# FPGA_PWR.net
KiCad netlist of a schematic drawn in Altium Designer
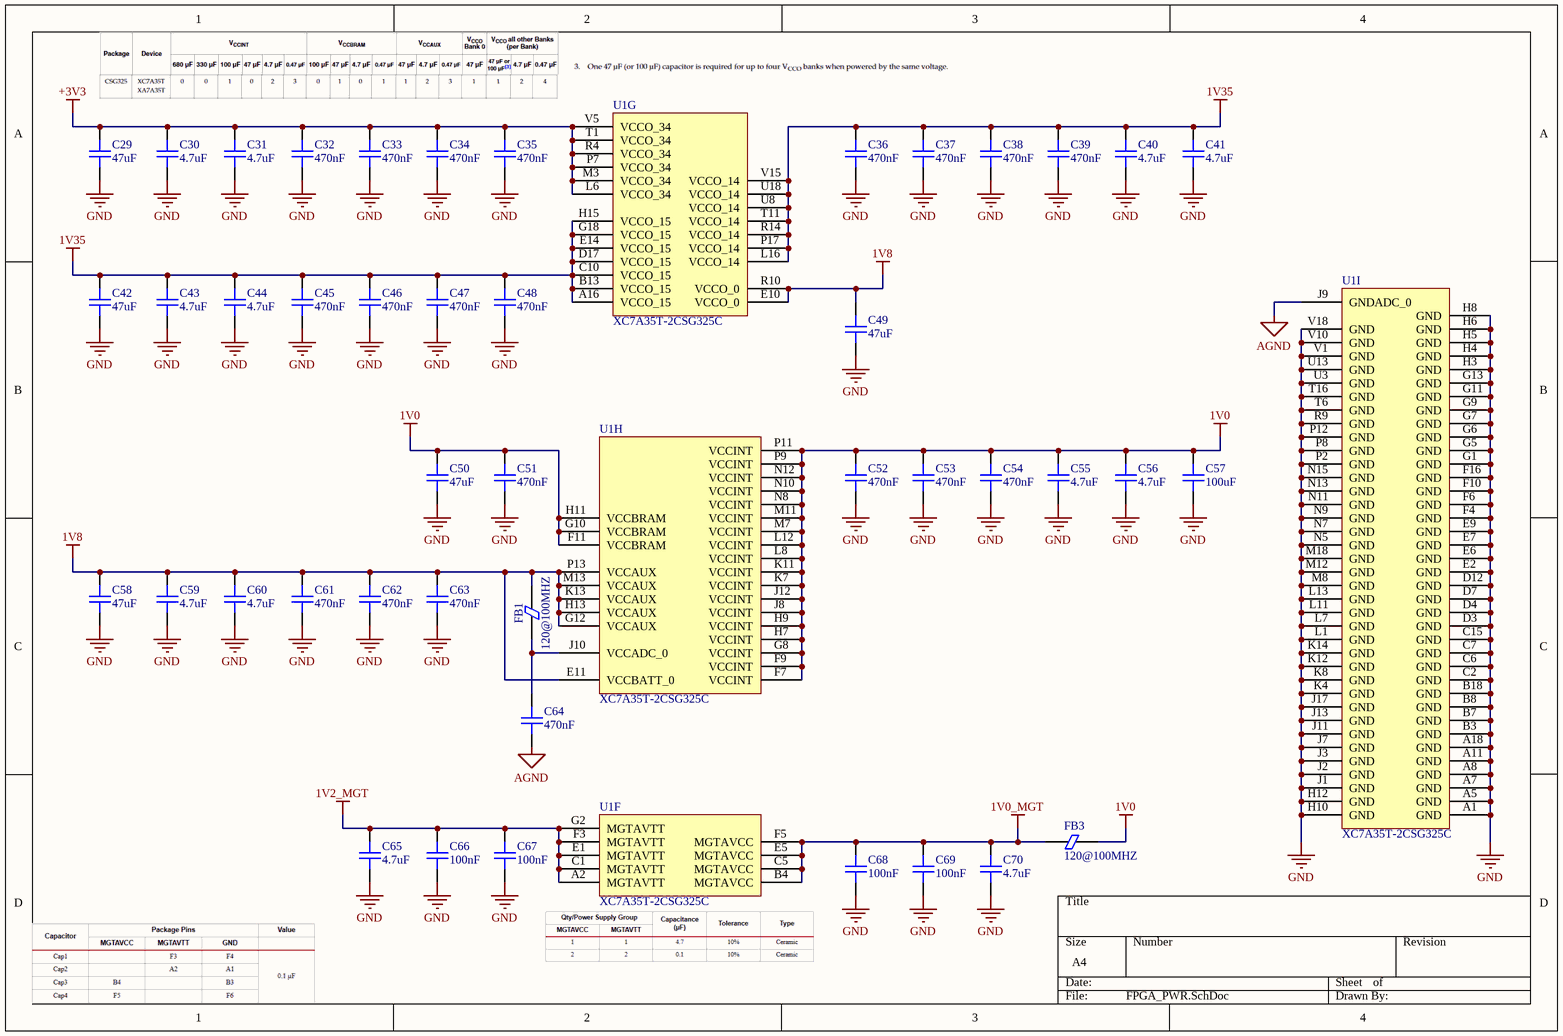
[diagram p0: FPGA_PWR.SchDoc]

(export (version "E")
  (design (tool "Eeschema 10.0.6"))
  (components
    (comp (ref "C29")
      (value "47uF")
      (footprint "GEN_C_0805")
      (libsource (lib "DSO") (part "CAP 47uF 6.3V X5R 0805"))
    )
    (comp (ref "C30")
      (value "4.7uF")
      (footprint "GEN_C_0402")
      (libsource (lib "DSO") (part "CAP 4.7uF 6.3V X5R 0402"))
    )
    (comp (ref "C31")
      (value "4.7uF")
      (footprint "GEN_C_0402")
      (libsource (lib "DSO") (part "CAP 4.7uF 6.3V X5R 0402"))
    )
    (comp (ref "C32")
      (value "470nF")
      (footprint "GEN_C_0201")
      (libsource (lib "DSO") (part "CAP 470nF 6.3V X5R 0201"))
    )
    (comp (ref "C33")
      (value "470nF")
      (footprint "GEN_C_0201")
      (libsource (lib "DSO") (part "CAP 470nF 6.3V X5R 0201"))
    )
    (comp (ref "C34")
      (value "470nF")
      (footprint "GEN_C_0201")
      (libsource (lib "DSO") (part "CAP 470nF 6.3V X5R 0201"))
    )
    (comp (ref "C35")
      (value "470nF")
      (footprint "GEN_C_0201")
      (libsource (lib "DSO") (part "CAP 470nF 6.3V X5R 0201"))
    )
    (comp (ref "C36")
      (value "470nF")
      (footprint "GEN_C_0201")
      (libsource (lib "DSO") (part "CAP 470nF 6.3V X5R 0201"))
    )
    (comp (ref "C37")
      (value "470nF")
      (footprint "GEN_C_0201")
      (libsource (lib "DSO") (part "CAP 470nF 6.3V X5R 0201"))
    )
    (comp (ref "C38")
      (value "470nF")
      (footprint "GEN_C_0201")
      (libsource (lib "DSO") (part "CAP 470nF 6.3V X5R 0201"))
    )
    (comp (ref "C39")
      (value "470nF")
      (footprint "GEN_C_0201")
      (libsource (lib "DSO") (part "CAP 470nF 6.3V X5R 0201"))
    )
    (comp (ref "C40")
      (value "4.7uF")
      (footprint "GEN_C_0402")
      (libsource (lib "DSO") (part "CAP 4.7uF 6.3V X5R 0402"))
    )
    (comp (ref "C41")
      (value "4.7uF")
      (footprint "GEN_C_0402")
      (libsource (lib "DSO") (part "CAP 4.7uF 6.3V X5R 0402"))
    )
    (comp (ref "C42")
      (value "47uF")
      (footprint "GEN_C_0805")
      (libsource (lib "DSO") (part "CAP 47uF 6.3V X5R 0805"))
    )
    (comp (ref "C43")
      (value "4.7uF")
      (footprint "GEN_C_0402")
      (libsource (lib "DSO") (part "CAP 4.7uF 6.3V X5R 0402"))
    )
    (comp (ref "C44")
      (value "4.7uF")
      (footprint "GEN_C_0402")
      (libsource (lib "DSO") (part "CAP 4.7uF 6.3V X5R 0402"))
    )
    (comp (ref "C45")
      (value "470nF")
      (footprint "GEN_C_0201")
      (libsource (lib "DSO") (part "CAP 470nF 6.3V X5R 0201"))
    )
    (comp (ref "C46")
      (value "470nF")
      (footprint "GEN_C_0201")
      (libsource (lib "DSO") (part "CAP 470nF 6.3V X5R 0201"))
    )
    (comp (ref "C47")
      (value "470nF")
      (footprint "GEN_C_0201")
      (libsource (lib "DSO") (part "CAP 470nF 6.3V X5R 0201"))
    )
    (comp (ref "C48")
      (value "470nF")
      (footprint "GEN_C_0201")
      (libsource (lib "DSO") (part "CAP 470nF 6.3V X5R 0201"))
    )
    (comp (ref "C49")
      (value "47uF")
      (footprint "GEN_C_0805")
      (libsource (lib "DSO") (part "CAP 47uF 6.3V X5R 0805"))
    )
    (comp (ref "C50")
      (value "47uF")
      (footprint "GEN_C_0805")
      (libsource (lib "DSO") (part "CAP 47uF 6.3V X5R 0805"))
    )
    (comp (ref "C51")
      (value "470nF")
      (footprint "GEN_C_0201")
      (libsource (lib "DSO") (part "CAP 470nF 6.3V X5R 0201"))
    )
    (comp (ref "C52")
      (value "470nF")
      (footprint "GEN_C_0201")
      (libsource (lib "DSO") (part "CAP 470nF 6.3V X5R 0201"))
    )
    (comp (ref "C53")
      (value "470nF")
      (footprint "GEN_C_0201")
      (libsource (lib "DSO") (part "CAP 470nF 6.3V X5R 0201"))
    )
    (comp (ref "C54")
      (value "470nF")
      (footprint "GEN_C_0201")
      (libsource (lib "DSO") (part "CAP 470nF 6.3V X5R 0201"))
    )
    (comp (ref "C55")
      (value "4.7uF")
      (footprint "GEN_C_0402")
      (libsource (lib "DSO") (part "CAP 4.7uF 6.3V X5R 0402"))
    )
    (comp (ref "C56")
      (value "4.7uF")
      (footprint "GEN_C_0402")
      (libsource (lib "DSO") (part "CAP 4.7uF 6.3V X5R 0402"))
    )
    (comp (ref "C57")
      (value "100uF")
      (footprint "GEN_C_1210")
      (libsource (lib "DSO") (part "CAP 100uF 6.3V X5R 1210"))
    )
    (comp (ref "C58")
      (value "47uF")
      (footprint "GEN_C_0805")
      (libsource (lib "DSO") (part "CAP 47uF 6.3V X5R 0805"))
    )
    (comp (ref "C59")
      (value "4.7uF")
      (footprint "GEN_C_0402")
      (libsource (lib "DSO") (part "CAP 4.7uF 6.3V X5R 0402"))
    )
    (comp (ref "C60")
      (value "4.7uF")
      (footprint "GEN_C_0402")
      (libsource (lib "DSO") (part "CAP 4.7uF 6.3V X5R 0402"))
    )
    (comp (ref "C61")
      (value "470nF")
      (footprint "GEN_C_0201")
      (libsource (lib "DSO") (part "CAP 470nF 6.3V X5R 0201"))
    )
    (comp (ref "C62")
      (value "470nF")
      (footprint "GEN_C_0201")
      (libsource (lib "DSO") (part "CAP 470nF 6.3V X5R 0201"))
    )
    (comp (ref "C63")
      (value "470nF")
      (footprint "GEN_C_0201")
      (libsource (lib "DSO") (part "CAP 470nF 6.3V X5R 0201"))
    )
    (comp (ref "C64")
      (value "470nF")
      (footprint "GEN_C_0201")
      (libsource (lib "DSO") (part "CAP 470nF 6.3V X5R 0201"))
    )
    (comp (ref "C65")
      (value "4.7uF")
      (footprint "GEN_C_0402")
      (libsource (lib "DSO") (part "CAP 4.7uF 6.3V X5R 0402"))
    )
    (comp (ref "C66")
      (value "100nF")
      (footprint "GEN_C_0201")
      (libsource (lib "DSO") (part "CAP 100nF 6.3V X5R 0201"))
    )
    (comp (ref "C67")
      (value "100nF")
      (footprint "GEN_C_0201")
      (libsource (lib "DSO") (part "CAP 100nF 6.3V X5R 0201"))
    )
    (comp (ref "C68")
      (value "100nF")
      (footprint "GEN_C_0201")
      (libsource (lib "DSO") (part "CAP 100nF 6.3V X5R 0201"))
    )
    (comp (ref "C69")
      (value "100nF")
      (footprint "GEN_C_0201")
      (libsource (lib "DSO") (part "CAP 100nF 6.3V X5R 0201"))
    )
    (comp (ref "C70")
      (value "4.7uF")
      (footprint "GEN_C_0402")
      (libsource (lib "DSO") (part "CAP 4.7uF 6.3V X5R 0402"))
    )
    (comp (ref "FB1")
      (value "120@100MHZ")
      (footprint "GEN_R_0402")
      (libsource (lib "DSO") (part "FERRITE BEAD 120 OHM 0402"))
    )
    (comp (ref "FB3")
      (value "120@100MHZ")
      (footprint "GEN_R_0402")
      (libsource (lib "DSO") (part "FERRITE BEAD 120 OHM 0402"))
    )
    (comp (ref "U1")
      (value "XC7A35T-2CSG325C")
      (footprint "CSG325")
      (description "Artix-7 FPGA, 150 User I/Os, 4 GTP, 324-Ball BGA, Speed Grade 2, Commercial Grade, Pb-Free")
      (fields (field (name "MANUFACTURER") "Xilinx"))
      (libsource (lib "Xilinx Artix-7") (part "XC7A35T-2CSG325C"))
    )
  )
  (nets
    (net (code "1") (name "+3V3") (class "Default")
      (node (ref "C29") (pin "2") (pinfunction "2_2") (pintype "passive"))
      (node (ref "C30") (pin "2") (pinfunction "2_2") (pintype "passive"))
      (node (ref "C31") (pin "2") (pinfunction "2_2") (pintype "passive"))
      (node (ref "C32") (pin "2") (pinfunction "2_2") (pintype "passive"))
      (node (ref "C33") (pin "2") (pinfunction "2_2") (pintype "passive"))
      (node (ref "C34") (pin "2") (pinfunction "2_2") (pintype "passive"))
      (node (ref "C35") (pin "2") (pinfunction "2_2") (pintype "passive"))
      (node (ref "U1") (pin "L6") (pinfunction "VCCO_34_L6") (pintype "power_in"))
      (node (ref "U1") (pin "M3") (pinfunction "VCCO_34_M3") (pintype "power_in"))
      (node (ref "U1") (pin "P7") (pinfunction "VCCO_34_P7") (pintype "power_in"))
      (node (ref "U1") (pin "R4") (pinfunction "VCCO_34_R4") (pintype "power_in"))
      (node (ref "U1") (pin "T1") (pinfunction "VCCO_34_T1") (pintype "power_in"))
      (node (ref "U1") (pin "V5") (pinfunction "VCCO_34_V5") (pintype "power_in"))
    )
    (net (code "2") (name "1V0") (class "Default")
      (node (ref "C50") (pin "2") (pinfunction "2_2") (pintype "passive"))
      (node (ref "C51") (pin "2") (pinfunction "2_2") (pintype "passive"))
      (node (ref "C52") (pin "2") (pinfunction "2_2") (pintype "passive"))
      (node (ref "C53") (pin "2") (pinfunction "2_2") (pintype "passive"))
      (node (ref "C54") (pin "2") (pinfunction "2_2") (pintype "passive"))
      (node (ref "C55") (pin "2") (pinfunction "2_2") (pintype "passive"))
      (node (ref "C56") (pin "2") (pinfunction "2_2") (pintype "passive"))
      (node (ref "C57") (pin "2") (pinfunction "2_2") (pintype "passive"))
      (node (ref "FB3") (pin "1") (pinfunction "1_1") (pintype "passive"))
      (node (ref "U1") (pin "F11") (pinfunction "VCCBRAM_F11") (pintype "power_in"))
      (node (ref "U1") (pin "F7") (pinfunction "VCCINT_F7") (pintype "power_in"))
      (node (ref "U1") (pin "F9") (pinfunction "VCCINT_F9") (pintype "power_in"))
      (node (ref "U1") (pin "G10") (pinfunction "VCCBRAM_G10") (pintype "power_in"))
      (node (ref "U1") (pin "G8") (pinfunction "VCCINT_G8") (pintype "power_in"))
      (node (ref "U1") (pin "H11") (pinfunction "VCCBRAM_H11") (pintype "power_in"))
      (node (ref "U1") (pin "H7") (pinfunction "VCCINT_H7") (pintype "power_in"))
      (node (ref "U1") (pin "H9") (pinfunction "VCCINT_H9") (pintype "power_in"))
      (node (ref "U1") (pin "J12") (pinfunction "VCCINT_J12") (pintype "power_in"))
      (node (ref "U1") (pin "J8") (pinfunction "VCCINT_J8") (pintype "power_in"))
      (node (ref "U1") (pin "K11") (pinfunction "VCCINT_K11") (pintype "power_in"))
      (node (ref "U1") (pin "K7") (pinfunction "VCCINT_K7") (pintype "power_in"))
      (node (ref "U1") (pin "L12") (pinfunction "VCCINT_L12") (pintype "power_in"))
      (node (ref "U1") (pin "L8") (pinfunction "VCCINT_L8") (pintype "power_in"))
      (node (ref "U1") (pin "M11") (pinfunction "VCCINT_M11") (pintype "power_in"))
      (node (ref "U1") (pin "M7") (pinfunction "VCCINT_M7") (pintype "power_in"))
      (node (ref "U1") (pin "N10") (pinfunction "VCCINT_N10") (pintype "power_in"))
      (node (ref "U1") (pin "N12") (pinfunction "VCCINT_N12") (pintype "power_in"))
      (node (ref "U1") (pin "N8") (pinfunction "VCCINT_N8") (pintype "power_in"))
      (node (ref "U1") (pin "P11") (pinfunction "VCCINT_P11") (pintype "power_in"))
      (node (ref "U1") (pin "P9") (pinfunction "VCCINT_P9") (pintype "power_in"))
    )
    (net (code "3") (name "1V0_MGT") (class "Default")
      (node (ref "C68") (pin "2") (pinfunction "2_2") (pintype "passive"))
      (node (ref "C69") (pin "2") (pinfunction "2_2") (pintype "passive"))
      (node (ref "C70") (pin "2") (pinfunction "2_2") (pintype "passive"))
      (node (ref "FB3") (pin "2") (pinfunction "2_2") (pintype "passive"))
      (node (ref "U1") (pin "B4") (pinfunction "MGTAVCC_B4") (pintype "power_in"))
      (node (ref "U1") (pin "C5") (pinfunction "MGTAVCC_C5") (pintype "power_in"))
      (node (ref "U1") (pin "E5") (pinfunction "MGTAVCC_E5") (pintype "power_in"))
      (node (ref "U1") (pin "F5") (pinfunction "MGTAVCC_F5") (pintype "power_in"))
    )
    (net (code "4") (name "1V2_MGT") (class "Default")
      (node (ref "C65") (pin "2") (pinfunction "2_2") (pintype "passive"))
      (node (ref "C66") (pin "2") (pinfunction "2_2") (pintype "passive"))
      (node (ref "C67") (pin "2") (pinfunction "2_2") (pintype "passive"))
      (node (ref "U1") (pin "A2") (pinfunction "MGTAVTT_A2") (pintype "power_in"))
      (node (ref "U1") (pin "C1") (pinfunction "MGTAVTT_C1") (pintype "power_in"))
      (node (ref "U1") (pin "E1") (pinfunction "MGTAVTT_E1") (pintype "power_in"))
      (node (ref "U1") (pin "F3") (pinfunction "MGTAVTT_F3") (pintype "power_in"))
      (node (ref "U1") (pin "G2") (pinfunction "MGTAVTT_G2") (pintype "power_in"))
    )
    (net (code "5") (name "1V8") (class "Default")
      (node (ref "C49") (pin "2") (pinfunction "2_2") (pintype "passive"))
      (node (ref "C58") (pin "2") (pinfunction "2_2") (pintype "passive"))
      (node (ref "C59") (pin "2") (pinfunction "2_2") (pintype "passive"))
      (node (ref "C60") (pin "2") (pinfunction "2_2") (pintype "passive"))
      (node (ref "C61") (pin "2") (pinfunction "2_2") (pintype "passive"))
      (node (ref "C62") (pin "2") (pinfunction "2_2") (pintype "passive"))
      (node (ref "C63") (pin "2") (pinfunction "2_2") (pintype "passive"))
      (node (ref "FB1") (pin "2") (pinfunction "2_2") (pintype "passive"))
      (node (ref "U1") (pin "E10") (pinfunction "VCCO_0_E10") (pintype "power_in"))
      (node (ref "U1") (pin "E11") (pinfunction "VCCBATT_0_E11") (pintype "power_in"))
      (node (ref "U1") (pin "G12") (pinfunction "VCCAUX_G12") (pintype "power_in"))
      (node (ref "U1") (pin "H13") (pinfunction "VCCAUX_H13") (pintype "power_in"))
      (node (ref "U1") (pin "K13") (pinfunction "VCCAUX_K13") (pintype "power_in"))
      (node (ref "U1") (pin "M13") (pinfunction "VCCAUX_M13") (pintype "power_in"))
      (node (ref "U1") (pin "P13") (pinfunction "VCCAUX_P13") (pintype "power_in"))
      (node (ref "U1") (pin "R10") (pinfunction "VCCO_0_R10") (pintype "power_in"))
    )
    (net (code "6") (name "1V35") (class "Default")
      (node (ref "C36") (pin "2") (pinfunction "2_2") (pintype "passive"))
      (node (ref "C37") (pin "2") (pinfunction "2_2") (pintype "passive"))
      (node (ref "C38") (pin "2") (pinfunction "2_2") (pintype "passive"))
      (node (ref "C39") (pin "2") (pinfunction "2_2") (pintype "passive"))
      (node (ref "C40") (pin "2") (pinfunction "2_2") (pintype "passive"))
      (node (ref "C41") (pin "2") (pinfunction "2_2") (pintype "passive"))
      (node (ref "C42") (pin "2") (pinfunction "2_2") (pintype "passive"))
      (node (ref "C43") (pin "2") (pinfunction "2_2") (pintype "passive"))
      (node (ref "C44") (pin "2") (pinfunction "2_2") (pintype "passive"))
      (node (ref "C45") (pin "2") (pinfunction "2_2") (pintype "passive"))
      (node (ref "C46") (pin "2") (pinfunction "2_2") (pintype "passive"))
      (node (ref "C47") (pin "2") (pinfunction "2_2") (pintype "passive"))
      (node (ref "C48") (pin "2") (pinfunction "2_2") (pintype "passive"))
      (node (ref "U1") (pin "A16") (pinfunction "VCCO_15_A16") (pintype "power_in"))
      (node (ref "U1") (pin "B13") (pinfunction "VCCO_15_B13") (pintype "power_in"))
      (node (ref "U1") (pin "C10") (pinfunction "VCCO_15_C10") (pintype "power_in"))
      (node (ref "U1") (pin "D17") (pinfunction "VCCO_15_D17") (pintype "power_in"))
      (node (ref "U1") (pin "E14") (pinfunction "VCCO_15_E14") (pintype "power_in"))
      (node (ref "U1") (pin "G18") (pinfunction "VCCO_15_G18") (pintype "power_in"))
      (node (ref "U1") (pin "H15") (pinfunction "VCCO_15_H15") (pintype "power_in"))
      (node (ref "U1") (pin "L16") (pinfunction "VCCO_14_L16") (pintype "power_in"))
      (node (ref "U1") (pin "P17") (pinfunction "VCCO_14_P17") (pintype "power_in"))
      (node (ref "U1") (pin "R14") (pinfunction "VCCO_14_R14") (pintype "power_in"))
      (node (ref "U1") (pin "T11") (pinfunction "VCCO_14_T11") (pintype "power_in"))
      (node (ref "U1") (pin "U18") (pinfunction "VCCO_14_U18") (pintype "power_in"))
      (node (ref "U1") (pin "U8") (pinfunction "VCCO_14_U8") (pintype "power_in"))
      (node (ref "U1") (pin "V15") (pinfunction "VCCO_14_V15") (pintype "power_in"))
    )
    (net (code "7") (name "AGND") (class "Default")
      (node (ref "C64") (pin "1") (pinfunction "1_1") (pintype "passive"))
      (node (ref "U1") (pin "J9") (pinfunction "GNDADC_0_J9") (pintype "power_in"))
    )
    (net (code "8") (name "GND") (class "Default")
      (node (ref "C29") (pin "1") (pinfunction "1_1") (pintype "passive"))
      (node (ref "C30") (pin "1") (pinfunction "1_1") (pintype "passive"))
      (node (ref "C31") (pin "1") (pinfunction "1_1") (pintype "passive"))
      (node (ref "C32") (pin "1") (pinfunction "1_1") (pintype "passive"))
      (node (ref "C33") (pin "1") (pinfunction "1_1") (pintype "passive"))
      (node (ref "C34") (pin "1") (pinfunction "1_1") (pintype "passive"))
      (node (ref "C35") (pin "1") (pinfunction "1_1") (pintype "passive"))
      (node (ref "C36") (pin "1") (pinfunction "1_1") (pintype "passive"))
      (node (ref "C37") (pin "1") (pinfunction "1_1") (pintype "passive"))
      (node (ref "C38") (pin "1") (pinfunction "1_1") (pintype "passive"))
      (node (ref "C39") (pin "1") (pinfunction "1_1") (pintype "passive"))
      (node (ref "C40") (pin "1") (pinfunction "1_1") (pintype "passive"))
      (node (ref "C41") (pin "1") (pinfunction "1_1") (pintype "passive"))
      (node (ref "C42") (pin "1") (pinfunction "1_1") (pintype "passive"))
      (node (ref "C43") (pin "1") (pinfunction "1_1") (pintype "passive"))
      (node (ref "C44") (pin "1") (pinfunction "1_1") (pintype "passive"))
      (node (ref "C45") (pin "1") (pinfunction "1_1") (pintype "passive"))
      (node (ref "C46") (pin "1") (pinfunction "1_1") (pintype "passive"))
      (node (ref "C47") (pin "1") (pinfunction "1_1") (pintype "passive"))
      (node (ref "C48") (pin "1") (pinfunction "1_1") (pintype "passive"))
      (node (ref "C49") (pin "1") (pinfunction "1_1") (pintype "passive"))
      (node (ref "C50") (pin "1") (pinfunction "1_1") (pintype "passive"))
      (node (ref "C51") (pin "1") (pinfunction "1_1") (pintype "passive"))
      (node (ref "C52") (pin "1") (pinfunction "1_1") (pintype "passive"))
      (node (ref "C53") (pin "1") (pinfunction "1_1") (pintype "passive"))
      (node (ref "C54") (pin "1") (pinfunction "1_1") (pintype "passive"))
      (node (ref "C55") (pin "1") (pinfunction "1_1") (pintype "passive"))
      (node (ref "C56") (pin "1") (pinfunction "1_1") (pintype "passive"))
      (node (ref "C57") (pin "1") (pinfunction "1_1") (pintype "passive"))
      (node (ref "C58") (pin "1") (pinfunction "1_1") (pintype "passive"))
      (node (ref "C59") (pin "1") (pinfunction "1_1") (pintype "passive"))
      (node (ref "C60") (pin "1") (pinfunction "1_1") (pintype "passive"))
      (node (ref "C61") (pin "1") (pinfunction "1_1") (pintype "passive"))
      (node (ref "C62") (pin "1") (pinfunction "1_1") (pintype "passive"))
      (node (ref "C63") (pin "1") (pinfunction "1_1") (pintype "passive"))
      (node (ref "C65") (pin "1") (pinfunction "1_1") (pintype "passive"))
      (node (ref "C66") (pin "1") (pinfunction "1_1") (pintype "passive"))
      (node (ref "C67") (pin "1") (pinfunction "1_1") (pintype "passive"))
      (node (ref "C68") (pin "1") (pinfunction "1_1") (pintype "passive"))
      (node (ref "C69") (pin "1") (pinfunction "1_1") (pintype "passive"))
      (node (ref "C70") (pin "1") (pinfunction "1_1") (pintype "passive"))
      (node (ref "U1") (pin "A1") (pinfunction "GND_A1") (pintype "power_in"))
      (node (ref "U1") (pin "A11") (pinfunction "GND_A11") (pintype "power_in"))
      (node (ref "U1") (pin "A18") (pinfunction "GND_A18") (pintype "power_in"))
      (node (ref "U1") (pin "A5") (pinfunction "GND_A5") (pintype "power_in"))
      (node (ref "U1") (pin "A7") (pinfunction "GND_A7") (pintype "power_in"))
      (node (ref "U1") (pin "A8") (pinfunction "GND_A8") (pintype "power_in"))
      (node (ref "U1") (pin "B18") (pinfunction "GND_B18") (pintype "power_in"))
      (node (ref "U1") (pin "B3") (pinfunction "GND_B3") (pintype "power_in"))
      (node (ref "U1") (pin "B7") (pinfunction "GND_B7") (pintype "power_in"))
      (node (ref "U1") (pin "B8") (pinfunction "GND_B8") (pintype "power_in"))
      (node (ref "U1") (pin "C15") (pinfunction "GND_C15") (pintype "power_in"))
      (node (ref "U1") (pin "C2") (pinfunction "GND_C2") (pintype "power_in"))
      (node (ref "U1") (pin "C6") (pinfunction "GND_C6") (pintype "power_in"))
      (node (ref "U1") (pin "C7") (pinfunction "GND_C7") (pintype "power_in"))
      (node (ref "U1") (pin "D12") (pinfunction "GND_D12") (pintype "power_in"))
      (node (ref "U1") (pin "D3") (pinfunction "GND_D3") (pintype "power_in"))
      (node (ref "U1") (pin "D4") (pinfunction "GND_D4") (pintype "power_in"))
      (node (ref "U1") (pin "D7") (pinfunction "GND_D7") (pintype "power_in"))
      (node (ref "U1") (pin "E2") (pinfunction "GND_E2") (pintype "power_in"))
      (node (ref "U1") (pin "E6") (pinfunction "GND_E6") (pintype "power_in"))
      (node (ref "U1") (pin "E7") (pinfunction "GND_E7") (pintype "power_in"))
      (node (ref "U1") (pin "E9") (pinfunction "GND_E9") (pintype "power_in"))
      (node (ref "U1") (pin "F10") (pinfunction "GND_F10") (pintype "power_in"))
      (node (ref "U1") (pin "F16") (pinfunction "GND_F16") (pintype "power_in"))
      (node (ref "U1") (pin "F4") (pinfunction "GND_F4") (pintype "power_in"))
      (node (ref "U1") (pin "F6") (pinfunction "GND_F6") (pintype "power_in"))
      (node (ref "U1") (pin "G1") (pinfunction "GND_G1") (pintype "power_in"))
      (node (ref "U1") (pin "G11") (pinfunction "GND_G11") (pintype "power_in"))
      (node (ref "U1") (pin "G13") (pinfunction "GND_G13") (pintype "power_in"))
      (node (ref "U1") (pin "G5") (pinfunction "GND_G5") (pintype "power_in"))
      (node (ref "U1") (pin "G6") (pinfunction "GND_G6") (pintype "power_in"))
      (node (ref "U1") (pin "G7") (pinfunction "GND_G7") (pintype "power_in"))
      (node (ref "U1") (pin "G9") (pinfunction "GND_G9") (pintype "power_in"))
      (node (ref "U1") (pin "H10") (pinfunction "GND_H10") (pintype "power_in"))
      (node (ref "U1") (pin "H12") (pinfunction "GND_H12") (pintype "power_in"))
      (node (ref "U1") (pin "H3") (pinfunction "GND_H3") (pintype "power_in"))
      (node (ref "U1") (pin "H4") (pinfunction "GND_H4") (pintype "power_in"))
      (node (ref "U1") (pin "H5") (pinfunction "GND_H5") (pintype "power_in"))
      (node (ref "U1") (pin "H6") (pinfunction "GND_H6") (pintype "power_in"))
      (node (ref "U1") (pin "H8") (pinfunction "GND_H8") (pintype "power_in"))
      (node (ref "U1") (pin "J1") (pinfunction "GND_J1") (pintype "power_in"))
      (node (ref "U1") (pin "J11") (pinfunction "GND_J11") (pintype "power_in"))
      (node (ref "U1") (pin "J13") (pinfunction "GND_J13") (pintype "power_in"))
      (node (ref "U1") (pin "J17") (pinfunction "GND_J17") (pintype "power_in"))
      (node (ref "U1") (pin "J2") (pinfunction "GND_J2") (pintype "power_in"))
      (node (ref "U1") (pin "J3") (pinfunction "GND_J3") (pintype "power_in"))
      (node (ref "U1") (pin "J7") (pinfunction "GND_J7") (pintype "power_in"))
      (node (ref "U1") (pin "K12") (pinfunction "GND_K12") (pintype "power_in"))
      (node (ref "U1") (pin "K14") (pinfunction "GND_K14") (pintype "power_in"))
      (node (ref "U1") (pin "K4") (pinfunction "GND_K4") (pintype "power_in"))
      (node (ref "U1") (pin "K8") (pinfunction "GND_K8") (pintype "power_in"))
      (node (ref "U1") (pin "L1") (pinfunction "GND_L1") (pintype "power_in"))
      (node (ref "U1") (pin "L11") (pinfunction "GND_L11") (pintype "power_in"))
      (node (ref "U1") (pin "L13") (pinfunction "GND_L13") (pintype "power_in"))
      (node (ref "U1") (pin "L7") (pinfunction "GND_L7") (pintype "power_in"))
      (node (ref "U1") (pin "M12") (pinfunction "GND_M12") (pintype "power_in"))
      (node (ref "U1") (pin "M18") (pinfunction "GND_M18") (pintype "power_in"))
      (node (ref "U1") (pin "M8") (pinfunction "GND_M8") (pintype "power_in"))
      (node (ref "U1") (pin "N11") (pinfunction "GND_N11") (pintype "power_in"))
      (node (ref "U1") (pin "N13") (pinfunction "GND_N13") (pintype "power_in"))
      (node (ref "U1") (pin "N15") (pinfunction "GND_N15") (pintype "power_in"))
      (node (ref "U1") (pin "N5") (pinfunction "GND_N5") (pintype "power_in"))
      (node (ref "U1") (pin "N7") (pinfunction "GND_N7") (pintype "power_in"))
      (node (ref "U1") (pin "N9") (pinfunction "GND_N9") (pintype "power_in"))
      (node (ref "U1") (pin "P12") (pinfunction "GND_P12") (pintype "power_in"))
      (node (ref "U1") (pin "P2") (pinfunction "GND_P2") (pintype "power_in"))
      (node (ref "U1") (pin "P8") (pinfunction "GND_P8") (pintype "power_in"))
      (node (ref "U1") (pin "R9") (pinfunction "GND_R9") (pintype "power_in"))
      (node (ref "U1") (pin "T16") (pinfunction "GND_T16") (pintype "power_in"))
      (node (ref "U1") (pin "T6") (pinfunction "GND_T6") (pintype "power_in"))
      (node (ref "U1") (pin "U13") (pinfunction "GND_U13") (pintype "power_in"))
      (node (ref "U1") (pin "U3") (pinfunction "GND_U3") (pintype "power_in"))
      (node (ref "U1") (pin "V1") (pinfunction "GND_V1") (pintype "power_in"))
      (node (ref "U1") (pin "V10") (pinfunction "GND_V10") (pintype "power_in"))
      (node (ref "U1") (pin "V18") (pinfunction "GND_V18") (pintype "power_in"))
    )
    (net (code "9") (name "Net-(U1H-VCCADC_0)") (class "Default")
      (node (ref "C64") (pin "2") (pinfunction "2_2") (pintype "passive"))
      (node (ref "FB1") (pin "1") (pinfunction "1_1") (pintype "passive"))
      (node (ref "U1") (pin "J10") (pinfunction "VCCADC_0_J10") (pintype "power_in"))
    )
  )
)
